# 238_power_measure102.net
KiCad netlist of a schematic drawn in EAGLE
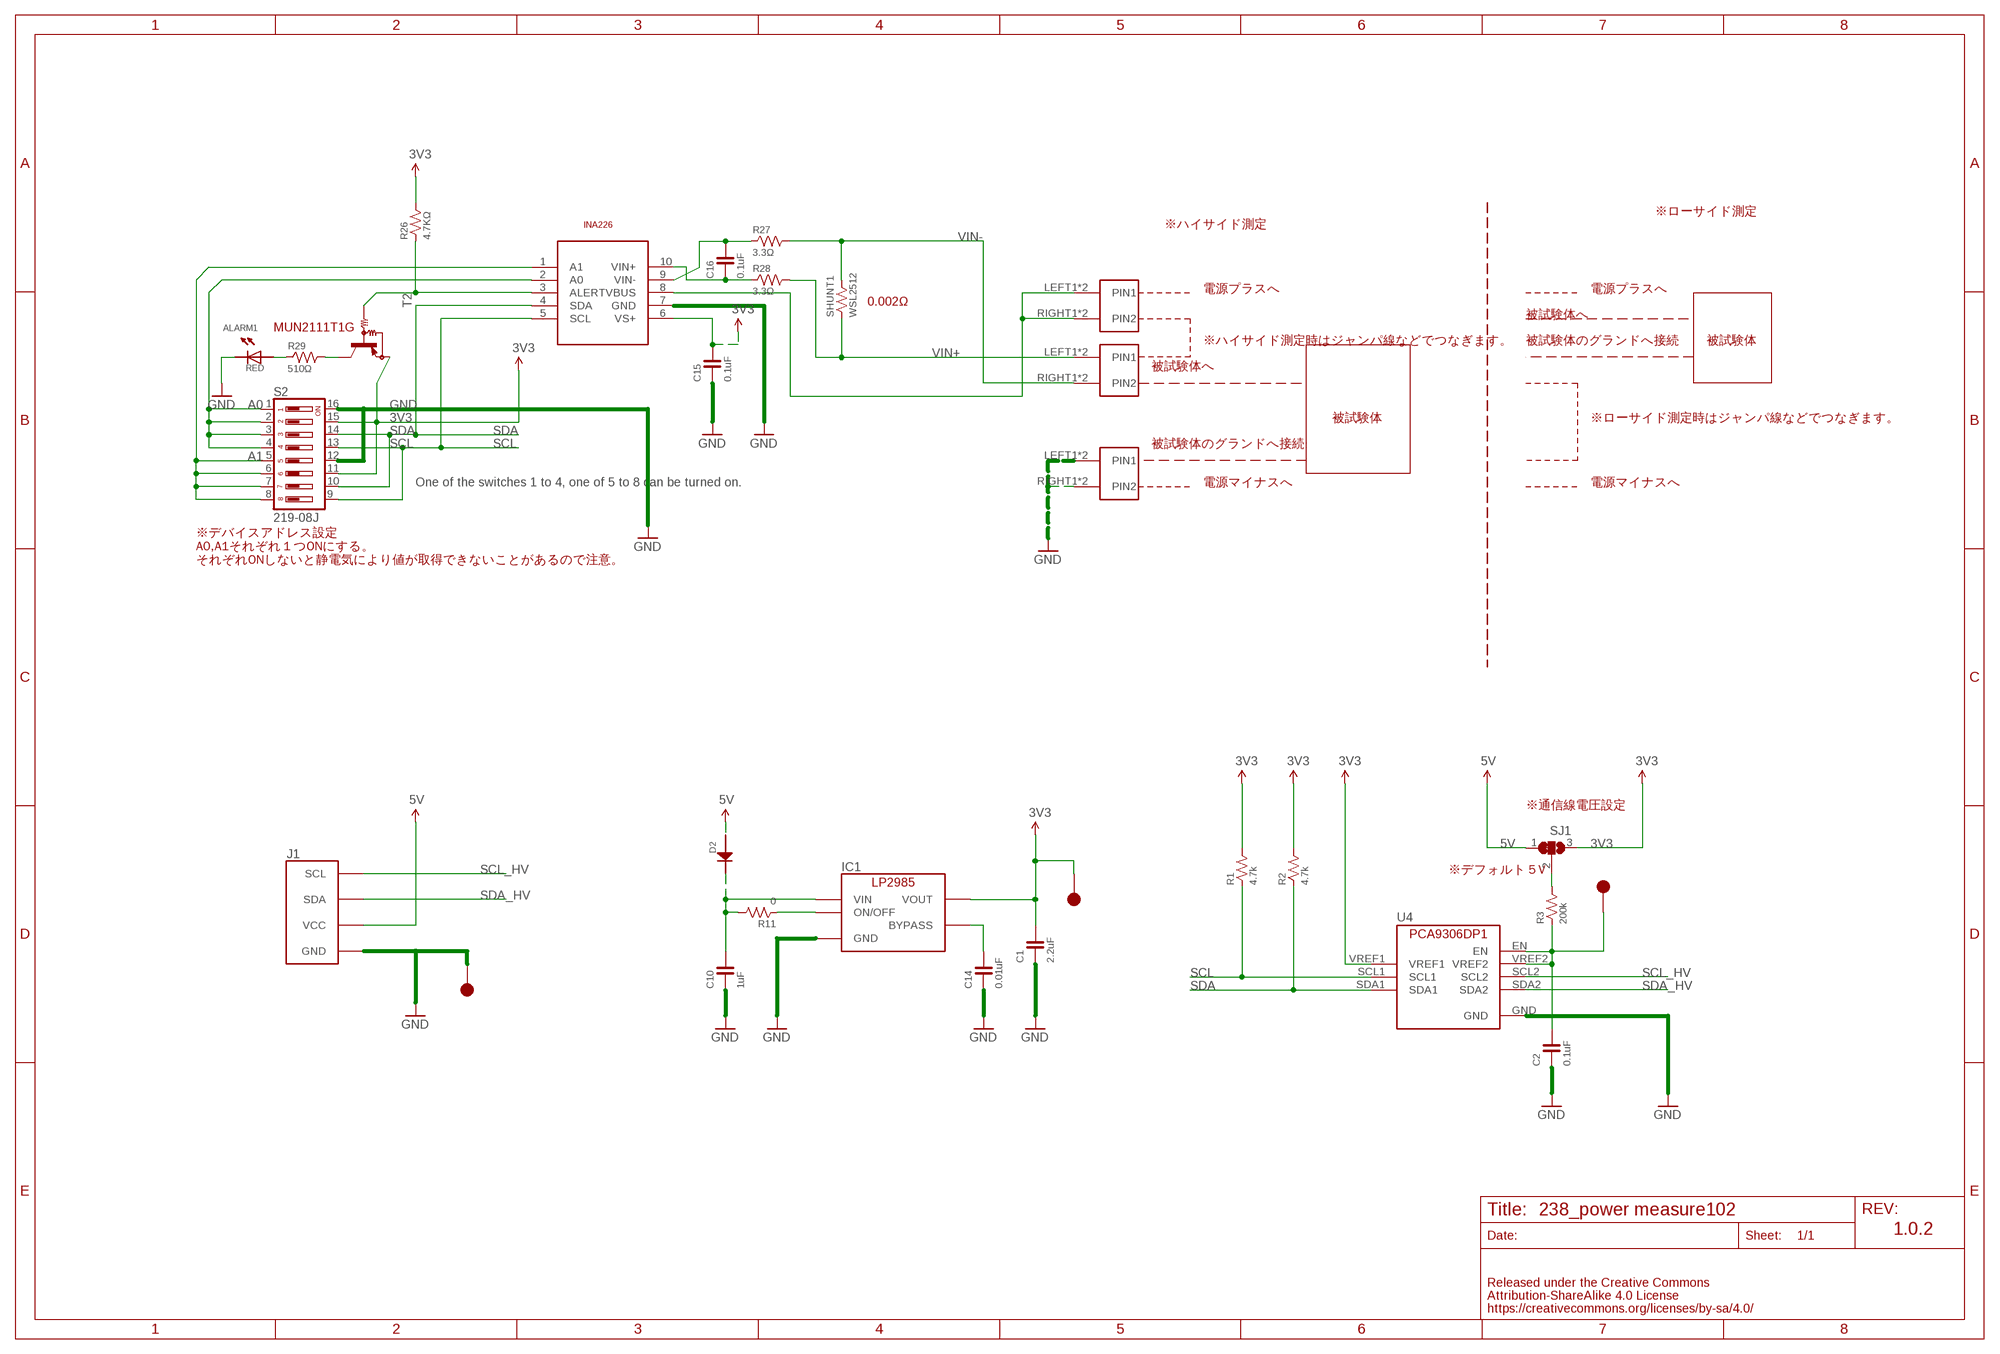
[diagram p0: schematic, sheet 1]

(export (version "E")
  (design (tool "Eeschema 10.0.6"))
  (components
    (comp (ref "ALARM1")
      (value "RED")
      (footprint "eagle-import:0603")
      (libsource (lib "eagle-import") (part "LED-0603"))
    )
    (comp (ref "C1")
      (value "2.2uF")
      (footprint "eagle-import:0603")
      (libsource (lib "eagle-import") (part "CAPACITOR-0603"))
    )
    (comp (ref "C2")
      (value "0.1uF")
      (footprint "eagle-import:0603")
      (libsource (lib "eagle-import") (part "CAPACITOR-0603"))
    )
    (comp (ref "C10")
      (value "1uF")
      (footprint "eagle-import:0603")
      (libsource (lib "eagle-import") (part "CAPACITOR-0603"))
    )
    (comp (ref "C14")
      (value "0.01uF")
      (footprint "eagle-import:0603")
      (libsource (lib "eagle-import") (part "CAPACITOR-0603"))
    )
    (comp (ref "C15")
      (value "0.1uF")
      (footprint "eagle-import:0603")
      (libsource (lib "eagle-import") (part "CAPACITOR-0603"))
    )
    (comp (ref "C16")
      (value "0.1uF")
      (footprint "eagle-import:0603")
      (libsource (lib "eagle-import") (part "CAPACITOR-0603"))
    )
    (comp (ref "D2")
      (value "1N4148")
      (footprint "eagle-import:1N4148W")
      (libsource (lib "eagle-import") (part "1N4148"))
    )
    (comp (ref "IC1")
      (value "LP2985-33")
      (footprint "eagle-import:SOT-23-5")
      (libsource (lib "eagle-import") (part "LP2985-33DBV"))
    )
    (comp (ref "J1")
      (value "FABO_BRICK_I2C-S04B-PASK-2")
      (footprint "eagle-import:FABO_BRICK_I2C_S04B-PASK-2")
      (libsource (lib "eagle-import") (part "FABO_BRICK_I2C-S04B-PASK-2"))
    )
    (comp (ref "R1")
      (value "4.7k")
      (footprint "eagle-import:0603")
      (libsource (lib "eagle-import") (part "RESISTOR-0603"))
    )
    (comp (ref "R2")
      (value "4.7k")
      (footprint "eagle-import:0603")
      (libsource (lib "eagle-import") (part "RESISTOR-0603"))
    )
    (comp (ref "R3")
      (value "200k")
      (footprint "eagle-import:0603")
      (libsource (lib "eagle-import") (part "RESISTOR-0603"))
    )
    (comp (ref "R11")
      (value "0")
      (footprint "eagle-import:0603")
      (libsource (lib "eagle-import") (part "RESISTOR-0603"))
    )
    (comp (ref "R26")
      (value "4.7KΩ")
      (footprint "eagle-import:0603")
      (libsource (lib "eagle-import") (part "RESISTOR-0603"))
    )
    (comp (ref "R27")
      (value "3.3Ω")
      (footprint "eagle-import:0603")
      (libsource (lib "eagle-import") (part "RESISTOR-0603"))
    )
    (comp (ref "R28")
      (value "3.3Ω")
      (footprint "eagle-import:0603")
      (libsource (lib "eagle-import") (part "RESISTOR-0603"))
    )
    (comp (ref "R29")
      (value "510Ω")
      (footprint "eagle-import:0603")
      (libsource (lib "eagle-import") (part "RESISTOR-0603"))
    )
    (comp (ref "S2")
      (value "219-08J")
      (footprint "eagle-import:CTS-219-08J")
      (libsource (lib "eagle-import") (part "219-08J"))
    )
    (comp (ref "SHUNT1")
      (value "WSL2512")
      (footprint "eagle-import:2512INCH")
      (libsource (lib "eagle-import") (part "WSL2512"))
    )
    (comp (ref "SJ1")
      (value "SJ2W")
      (footprint "eagle-import:SJ_2")
      (libsource (lib "eagle-import") (part "SJ2W"))
    )
    (comp (ref "T2")
      (value "MUN2111T1-PNP_DRIVER-SC59-BEC")
      (footprint "eagle-import:SC59-BEC")
      (libsource (lib "eagle-import") (part "-PNP_DRIVER-SC59-BECMUN2111T1"))
    )
    (comp (ref "TP1")
      (value "TP-15")
      (footprint "eagle-import:TP-15")
      (libsource (lib "eagle-import") (part "TP-15"))
    )
    (comp (ref "TP2")
      (value "TP-15")
      (footprint "eagle-import:TP-15")
      (libsource (lib "eagle-import") (part "TP-15"))
    )
    (comp (ref "TP5")
      (value "TP-15")
      (footprint "eagle-import:TP-15")
      (libsource (lib "eagle-import") (part "TP-15"))
    )
    (comp (ref "U$23")
      (value "ML-1400-S1")
      (footprint "eagle-import:ML-1400-S1")
      (libsource (lib "eagle-import") (part "ML-1400-S1"))
    )
    (comp (ref "U$24")
      (value "ML-1400-S1")
      (footprint "eagle-import:ML-1400-S1")
      (libsource (lib "eagle-import") (part "ML-1400-S1"))
    )
    (comp (ref "U$25")
      (value "ML-1400-S1")
      (footprint "eagle-import:ML-1400-S1")
      (libsource (lib "eagle-import") (part "ML-1400-S1"))
    )
    (comp (ref "U3")
      (value "TI-INA226")
      (footprint "eagle-import:TI-INA226")
      (libsource (lib "eagle-import") (part "TI-INA226"))
    )
    (comp (ref "U4")
      (value "PCA9306DP1")
      (footprint "eagle-import:TSSOP8")
      (libsource (lib "eagle-import") (part "PCA9306DP1"))
    )
  )
  (nets
    (net (code "1") (name "/A0") (class "Default")
      (node (ref "S2") (pin "1") (pinfunction "1_1") (pintype "passive"))
      (node (ref "S2") (pin "2") (pinfunction "2_2") (pintype "passive"))
      (node (ref "S2") (pin "3") (pinfunction "3_3") (pintype "passive"))
      (node (ref "S2") (pin "4") (pinfunction "4_4") (pintype "passive"))
      (node (ref "U3") (pin "2") (pinfunction "A0_2") (pintype "bidirectional"))
    )
    (net (code "2") (name "/A1") (class "Default")
      (node (ref "S2") (pin "5") (pinfunction "5_5") (pintype "passive"))
      (node (ref "S2") (pin "6") (pinfunction "6_6") (pintype "passive"))
      (node (ref "S2") (pin "7") (pinfunction "7_7") (pintype "passive"))
      (node (ref "S2") (pin "8") (pinfunction "8_8") (pintype "passive"))
      (node (ref "U3") (pin "1") (pinfunction "A1_1") (pintype "bidirectional"))
    )
    (net (code "3") (name "/SCL") (class "Default")
      (node (ref "R1") (pin "1") (pinfunction "1_1") (pintype "bidirectional"))
      (node (ref "S2") (pin "13") (pinfunction "13_13") (pintype "passive"))
      (node (ref "S2") (pin "9") (pinfunction "9_9") (pintype "passive"))
      (node (ref "U3") (pin "5") (pinfunction "SCL_5") (pintype "bidirectional"))
      (node (ref "U4") (pin "SCL1") (pinfunction "SCL1_SCL1") (pintype "bidirectional"))
    )
    (net (code "4") (name "/SCL_HV") (class "Default")
      (node (ref "J1") (pin "SCL") (pinfunction "SCL_SCL") (pintype "bidirectional"))
      (node (ref "U4") (pin "SCL2") (pinfunction "SCL2_SCL2") (pintype "bidirectional"))
    )
    (net (code "5") (name "/SDA") (class "Default")
      (node (ref "R2") (pin "1") (pinfunction "1_1") (pintype "bidirectional"))
      (node (ref "S2") (pin "10") (pinfunction "10_10") (pintype "passive"))
      (node (ref "S2") (pin "14") (pinfunction "14_14") (pintype "passive"))
      (node (ref "U3") (pin "4") (pinfunction "SDA_4") (pintype "bidirectional"))
      (node (ref "U4") (pin "SDA1") (pinfunction "SDA1_SDA1") (pintype "bidirectional"))
    )
    (net (code "6") (name "/SDA_HV") (class "Default")
      (node (ref "J1") (pin "SDA") (pinfunction "SDA_SDA") (pintype "bidirectional"))
      (node (ref "U4") (pin "SDA2") (pinfunction "SDA2_SDA2") (pintype "bidirectional"))
    )
    (net (code "7") (name "/VIN+") (class "Default")
      (node (ref "R28") (pin "2") (pinfunction "2_2") (pintype "bidirectional"))
      (node (ref "SHUNT1") (pin "P$1") (pinfunction "1_P$1") (pintype "bidirectional"))
      (node (ref "U$24") (pin "LEFT1") (pinfunction "PIN1_LEFT1") (pintype "bidirectional"))
      (node (ref "U$24") (pin "LEFT2") (pinfunction "PIN1_LEFT2") (pintype "bidirectional"))
    )
    (net (code "8") (name "/VIN-") (class "Default")
      (node (ref "R27") (pin "2") (pinfunction "2_2") (pintype "bidirectional"))
      (node (ref "SHUNT1") (pin "P$2") (pinfunction "2_P$2") (pintype "bidirectional"))
      (node (ref "U$24") (pin "RIGHT1") (pinfunction "PIN2_RIGHT1") (pintype "bidirectional"))
      (node (ref "U$24") (pin "RIGHT2") (pinfunction "PIN2_RIGHT2") (pintype "bidirectional"))
    )
    (net (code "9") (name "3V3") (class "Default")
      (node (ref "C1") (pin "2") (pinfunction "2_2") (pintype "passive"))
      (node (ref "C15") (pin "2") (pinfunction "2_2") (pintype "passive"))
      (node (ref "IC1") (pin "5") (pinfunction "VOUT_5") (pintype "output"))
      (node (ref "R1") (pin "2") (pinfunction "2_2") (pintype "bidirectional"))
      (node (ref "R2") (pin "2") (pinfunction "2_2") (pintype "bidirectional"))
      (node (ref "R26") (pin "2") (pinfunction "2_2") (pintype "bidirectional"))
      (node (ref "S2") (pin "11") (pinfunction "11_11") (pintype "passive"))
      (node (ref "S2") (pin "15") (pinfunction "15_15") (pintype "passive"))
      (node (ref "SJ1") (pin "3") (pinfunction "3_3") (pintype "passive"))
      (node (ref "T2") (pin "E") (pinfunction "E_E") (pintype "passive"))
      (node (ref "TP5") (pin "1") (pinfunction "1_1") (pintype "bidirectional"))
      (node (ref "U3") (pin "6") (pinfunction "VS+_6") (pintype "bidirectional"))
      (node (ref "U4") (pin "VREF1") (pinfunction "VREF1_VREF1") (pintype "bidirectional"))
    )
    (net (code "10") (name "5V") (class "Default")
      (node (ref "D2") (pin "ANODE") (pinfunction "ANODE_ANODE") (pintype "bidirectional"))
      (node (ref "J1") (pin "VCC") (pinfunction "VCC_VCC") (pintype "bidirectional"))
      (node (ref "SJ1") (pin "1") (pinfunction "1_1") (pintype "passive"))
    )
    (net (code "11") (name "GND") (class "Default")
      (node (ref "ALARM1") (pin "CATHODE") (pinfunction "CATHODE_CATHODE") (pintype "passive"))
      (node (ref "C1") (pin "1") (pinfunction "1_1") (pintype "passive"))
      (node (ref "C10") (pin "1") (pinfunction "1_1") (pintype "passive"))
      (node (ref "C14") (pin "1") (pinfunction "1_1") (pintype "passive"))
      (node (ref "C15") (pin "1") (pinfunction "1_1") (pintype "passive"))
      (node (ref "C2") (pin "1") (pinfunction "1_1") (pintype "passive"))
      (node (ref "IC1") (pin "2") (pinfunction "GND_2") (pintype "power_in"))
      (node (ref "J1") (pin "GND") (pinfunction "GND_GND") (pintype "bidirectional"))
      (node (ref "S2") (pin "12") (pinfunction "12_12") (pintype "passive"))
      (node (ref "S2") (pin "16") (pinfunction "16_16") (pintype "passive"))
      (node (ref "TP1") (pin "1") (pinfunction "1_1") (pintype "bidirectional"))
      (node (ref "U$25") (pin "LEFT1") (pinfunction "PIN1_LEFT1") (pintype "bidirectional"))
      (node (ref "U$25") (pin "LEFT2") (pinfunction "PIN1_LEFT2") (pintype "bidirectional"))
      (node (ref "U$25") (pin "RIGHT1") (pinfunction "PIN2_RIGHT1") (pintype "bidirectional"))
      (node (ref "U$25") (pin "RIGHT2") (pinfunction "PIN2_RIGHT2") (pintype "bidirectional"))
      (node (ref "U3") (pin "7") (pinfunction "GND_7") (pintype "bidirectional"))
      (node (ref "U4") (pin "GND") (pinfunction "GND_GND") (pintype "bidirectional"))
    )
    (net (code "12") (name "Net-(ALARM1-PadANODE)") (class "Default")
      (node (ref "ALARM1") (pin "ANODE") (pinfunction "ANODE_ANODE") (pintype "passive"))
      (node (ref "R29") (pin "1") (pinfunction "1_1") (pintype "bidirectional"))
    )
    (net (code "13") (name "Net-(C2-Pad2)") (class "Default")
      (node (ref "C2") (pin "2") (pinfunction "2_2") (pintype "passive"))
      (node (ref "R3") (pin "1") (pinfunction "1_1") (pintype "bidirectional"))
      (node (ref "TP2") (pin "1") (pinfunction "1_1") (pintype "bidirectional"))
      (node (ref "U4") (pin "EN") (pinfunction "EN_EN") (pintype "bidirectional"))
      (node (ref "U4") (pin "VREF2") (pinfunction "VREF2_VREF2") (pintype "bidirectional"))
    )
    (net (code "14") (name "Net-(IC1-BYPASS)") (class "Default")
      (node (ref "C14") (pin "2") (pinfunction "2_2") (pintype "passive"))
      (node (ref "IC1") (pin "4") (pinfunction "BYPASS_4") (pintype "bidirectional"))
    )
    (net (code "15") (name "Net-(IC1-ON{slash}OFF)") (class "Default")
      (node (ref "IC1") (pin "3") (pinfunction "ON/OFF_3") (pintype "input"))
      (node (ref "R11") (pin "1") (pinfunction "1_1") (pintype "bidirectional"))
    )
    (net (code "16") (name "Net-(IC1-VIN)") (class "Default")
      (node (ref "C10") (pin "2") (pinfunction "2_2") (pintype "passive"))
      (node (ref "D2") (pin "CATHODE") (pinfunction "CATHODE_CATHODE") (pintype "bidirectional"))
      (node (ref "IC1") (pin "1") (pinfunction "VIN_1") (pintype "input"))
      (node (ref "R11") (pin "2") (pinfunction "2_2") (pintype "bidirectional"))
    )
    (net (code "17") (name "Net-(R3-Pad2)") (class "Default")
      (node (ref "R3") (pin "2") (pinfunction "2_2") (pintype "bidirectional"))
      (node (ref "SJ1") (pin "2") (pinfunction "2_2") (pintype "passive"))
    )
    (net (code "18") (name "Net-(R29-Pad2)") (class "Default")
      (node (ref "R29") (pin "2") (pinfunction "2_2") (pintype "bidirectional"))
      (node (ref "T2") (pin "C") (pinfunction "C_C") (pintype "passive"))
    )
    (net (code "19") (name "Net-(U3-ALERT)") (class "Default")
      (node (ref "R26") (pin "1") (pinfunction "1_1") (pintype "bidirectional"))
      (node (ref "T2") (pin "B") (pinfunction "B_B") (pintype "passive"))
      (node (ref "U3") (pin "3") (pinfunction "ALERT_3") (pintype "bidirectional"))
    )
    (net (code "20") (name "Net-(U3-VBUS)") (class "Default")
      (node (ref "U$23") (pin "LEFT1") (pinfunction "PIN1_LEFT1") (pintype "bidirectional"))
      (node (ref "U$23") (pin "LEFT2") (pinfunction "PIN1_LEFT2") (pintype "bidirectional"))
      (node (ref "U$23") (pin "RIGHT1") (pinfunction "PIN2_RIGHT1") (pintype "bidirectional"))
      (node (ref "U$23") (pin "RIGHT2") (pinfunction "PIN2_RIGHT2") (pintype "bidirectional"))
      (node (ref "U3") (pin "8") (pinfunction "VBUS_8") (pintype "bidirectional"))
    )
    (net (code "21") (name "Net-(U3-VIN+)") (class "Default")
      (node (ref "C16") (pin "1") (pinfunction "1_1") (pintype "passive"))
      (node (ref "R28") (pin "1") (pinfunction "1_1") (pintype "bidirectional"))
      (node (ref "U3") (pin "10") (pinfunction "VIN+_10") (pintype "bidirectional"))
    )
    (net (code "22") (name "Net-(U3-VIN-)") (class "Default")
      (node (ref "C16") (pin "2") (pinfunction "2_2") (pintype "passive"))
      (node (ref "R27") (pin "1") (pinfunction "1_1") (pintype "bidirectional"))
      (node (ref "U3") (pin "9") (pinfunction "VIN-_9") (pintype "bidirectional"))
    )
  )
)
